# Schematic.net
KiCad netlist of a schematic drawn in EAGLE
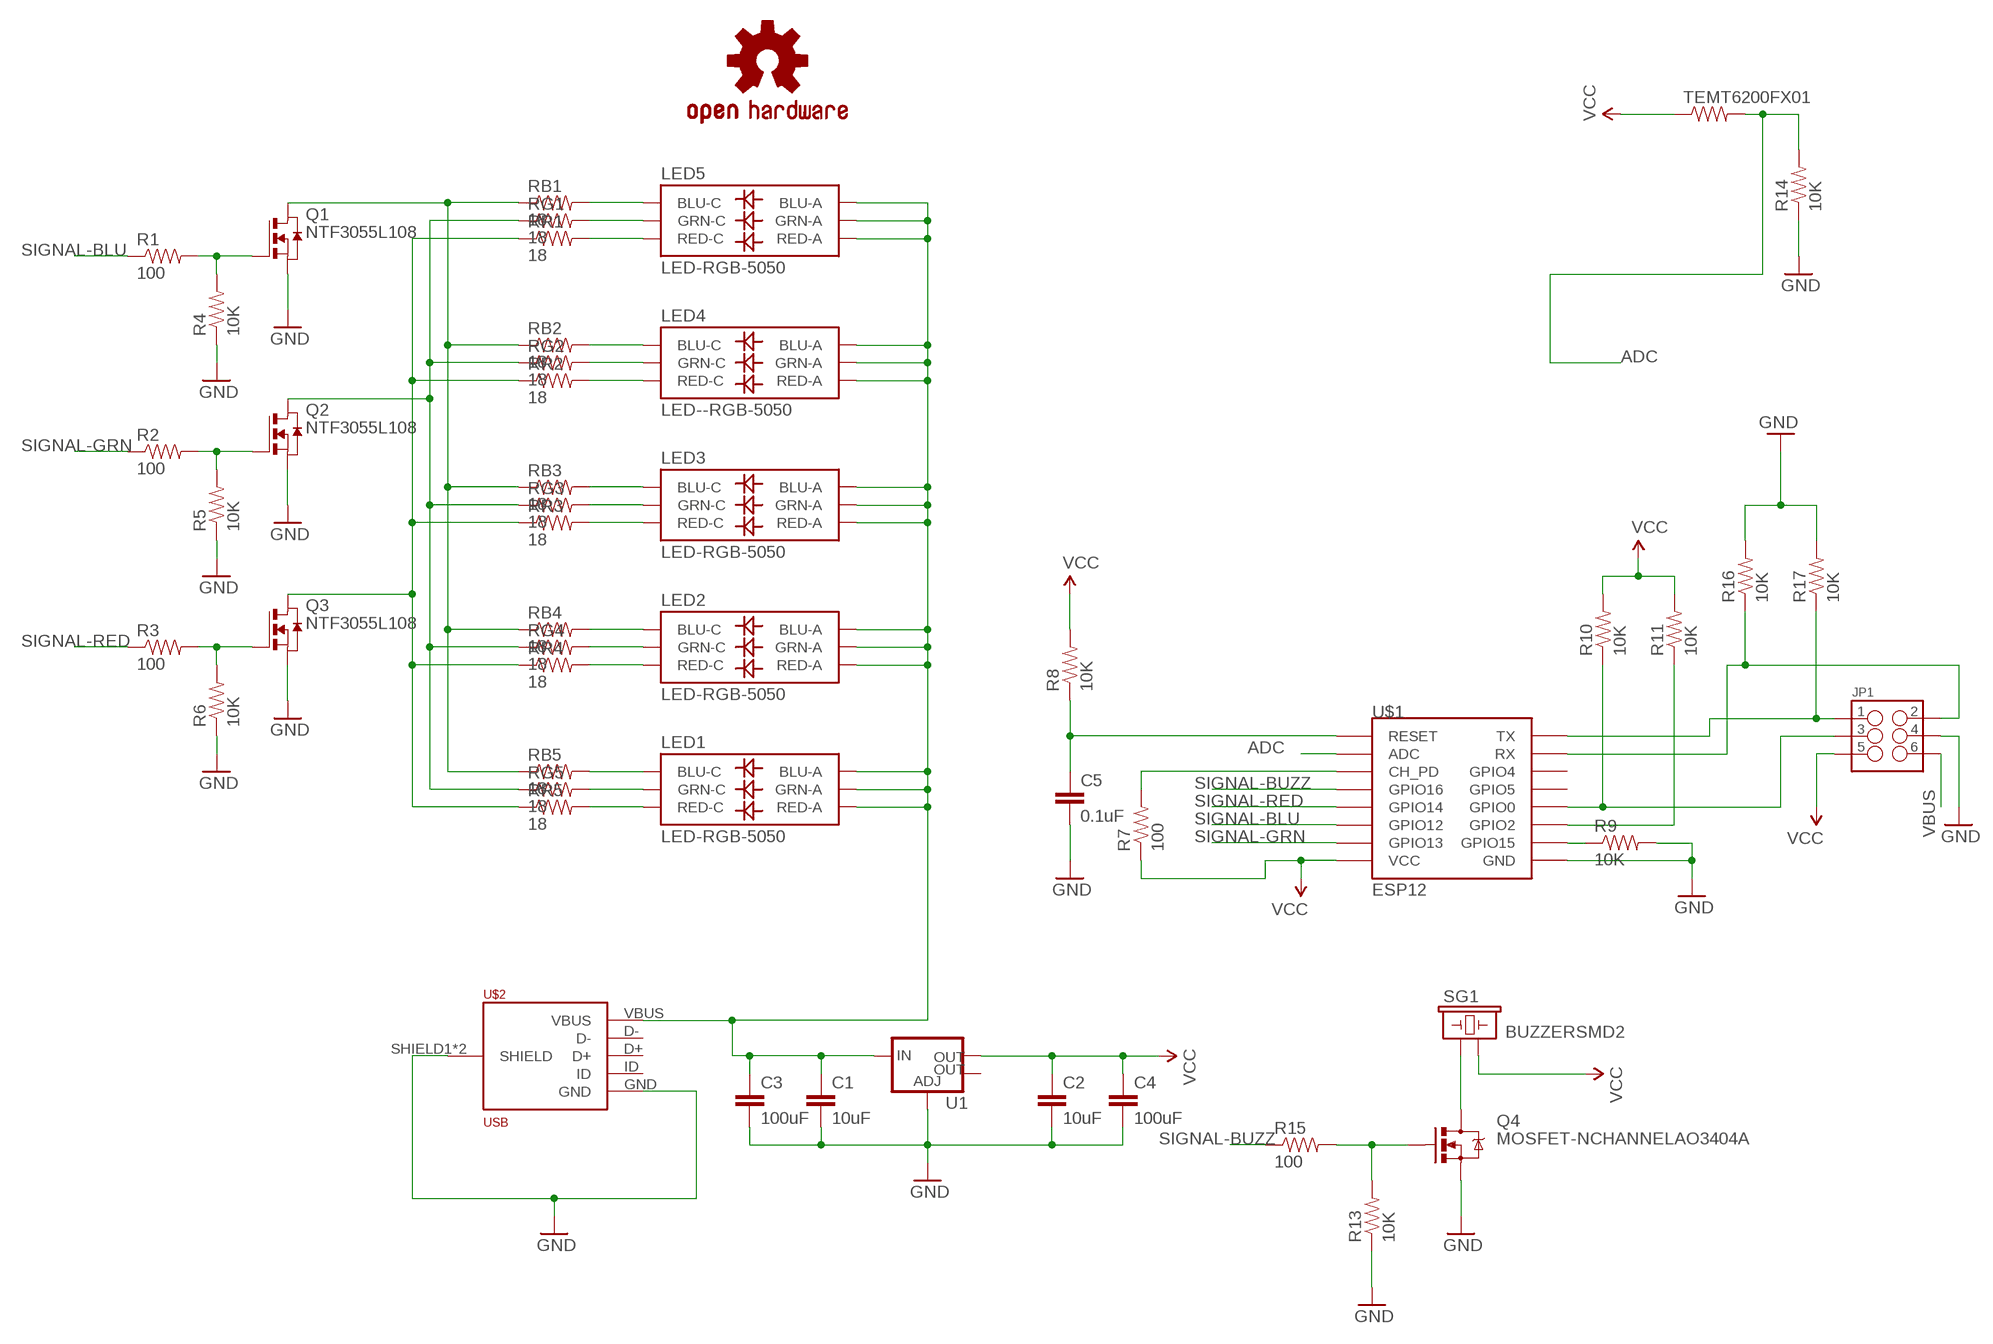
[diagram p0: schematic, sheet 1]

(export (version "E")
  (design (tool "Eeschema 10.0.6"))
  (components
    (comp (ref "C1")
      (value "10uF")
      (footprint "eagle-import:0603-CAP")
      (libsource (lib "eagle-import") (part "CAP0603-CAP"))
    )
    (comp (ref "C2")
      (value "10uF")
      (footprint "eagle-import:0603-CAP")
      (libsource (lib "eagle-import") (part "CAP0603-CAP"))
    )
    (comp (ref "C3")
      (value "100uF")
      (footprint "eagle-import:1206")
      (libsource (lib "eagle-import") (part "CAP1206"))
    )
    (comp (ref "C4")
      (value "100uF")
      (footprint "eagle-import:1206")
      (libsource (lib "eagle-import") (part "CAP1206"))
    )
    (comp (ref "C5")
      (value "0.1uF")
      (footprint "eagle-import:0603-CAP")
      (libsource (lib "eagle-import") (part "CAP0603-CAP"))
    )
    (comp (ref "JP1")
      (value "M03X2POGO_PINS")
      (footprint "eagle-import:2X3_POGO")
      (libsource (lib "eagle-import") (part "M03X2POGO_PINS"))
    )
    (comp (ref "LED1")
      (value "LED-RGB-5050")
      (footprint "eagle-import:LED-TRICOLOR-5050")
      (libsource (lib "eagle-import") (part "LED-TRICOLOR-5050NO_IC"))
    )
    (comp (ref "LED2")
      (value "LED-RGB-5050")
      (footprint "eagle-import:LED-TRICOLOR-5050")
      (libsource (lib "eagle-import") (part "LED-TRICOLOR-5050NO_IC"))
    )
    (comp (ref "LED3")
      (value "LED-RGB-5050")
      (footprint "eagle-import:LED-TRICOLOR-5050")
      (libsource (lib "eagle-import") (part "LED-TRICOLOR-5050NO_IC"))
    )
    (comp (ref "LED4")
      (value "LED--RGB-5050")
      (footprint "eagle-import:LED-TRICOLOR-5050")
      (libsource (lib "eagle-import") (part "LED-TRICOLOR-5050NO_IC"))
    )
    (comp (ref "LED5")
      (value "LED-RGB-5050")
      (footprint "eagle-import:LED-TRICOLOR-5050")
      (libsource (lib "eagle-import") (part "LED-TRICOLOR-5050NO_IC"))
    )
    (comp (ref "LOGO1")
      (value "OSHW-LOGOM-COPPER")
      (footprint "eagle-import:OSHW-LOGO-M_COPPER")
      (libsource (lib "eagle-import") (part "OSHW-LOGOM-COPPER"))
    )
    (comp (ref "Q1")
      (value "NTF3055L108")
      (footprint "eagle-import:SOT223HEAT")
      (libsource (lib "eagle-import") (part "NMOSSOT223'HEATSINK'"))
    )
    (comp (ref "Q2")
      (value "NTF3055L108")
      (footprint "eagle-import:SOT223HEAT")
      (libsource (lib "eagle-import") (part "NMOSSOT223'HEATSINK'"))
    )
    (comp (ref "Q3")
      (value "NTF3055L108")
      (footprint "eagle-import:SOT223HEAT")
      (libsource (lib "eagle-import") (part "NMOSSOT223'HEATSINK'"))
    )
    (comp (ref "Q4")
      (value "MOSFET-NCHANNELAO3404A")
      (footprint "eagle-import:SOT23-3")
      (libsource (lib "eagle-import") (part "MOSFET-NCHANNELAO3404A"))
    )
    (comp (ref "R1")
      (value "100")
      (footprint "eagle-import:0805")
      (libsource (lib "eagle-import") (part "RESISTOR0805-RES"))
    )
    (comp (ref "R2")
      (value "100")
      (footprint "eagle-import:0805")
      (libsource (lib "eagle-import") (part "RESISTOR0805-RES"))
    )
    (comp (ref "R3")
      (value "100")
      (footprint "eagle-import:0805")
      (libsource (lib "eagle-import") (part "RESISTOR0805-RES"))
    )
    (comp (ref "R4")
      (value "10K")
      (footprint "eagle-import:0805")
      (libsource (lib "eagle-import") (part "RESISTOR0805-RES"))
    )
    (comp (ref "R5")
      (value "10K")
      (footprint "eagle-import:0805")
      (libsource (lib "eagle-import") (part "RESISTOR0805-RES"))
    )
    (comp (ref "R6")
      (value "10K")
      (footprint "eagle-import:0805")
      (libsource (lib "eagle-import") (part "RESISTOR0805-RES"))
    )
    (comp (ref "R7")
      (value "100")
      (footprint "eagle-import:0805")
      (libsource (lib "eagle-import") (part "RESISTOR0805-RES"))
    )
    (comp (ref "R8")
      (value "10K")
      (footprint "eagle-import:0805")
      (libsource (lib "eagle-import") (part "RESISTOR0805-RES"))
    )
    (comp (ref "R9")
      (value "10K")
      (footprint "eagle-import:0805")
      (libsource (lib "eagle-import") (part "RESISTOR0805-RES"))
    )
    (comp (ref "R10")
      (value "10K")
      (footprint "eagle-import:0805")
      (libsource (lib "eagle-import") (part "RESISTOR0805-RES"))
    )
    (comp (ref "R11")
      (value "10K")
      (footprint "eagle-import:0805")
      (libsource (lib "eagle-import") (part "RESISTOR0805-RES"))
    )
    (comp (ref "R13")
      (value "10K")
      (footprint "eagle-import:0805")
      (libsource (lib "eagle-import") (part "RESISTOR0805-RES"))
    )
    (comp (ref "R14")
      (value "10K")
      (footprint "eagle-import:0805")
      (libsource (lib "eagle-import") (part "RESISTOR0805-RES"))
    )
    (comp (ref "R15")
      (value "100")
      (footprint "eagle-import:0805")
      (libsource (lib "eagle-import") (part "RESISTOR0805-RES"))
    )
    (comp (ref "R16")
      (value "10K")
      (footprint "eagle-import:0805")
      (libsource (lib "eagle-import") (part "RESISTOR0805-RES"))
    )
    (comp (ref "R17")
      (value "10K")
      (footprint "eagle-import:0805")
      (libsource (lib "eagle-import") (part "RESISTOR0805-RES"))
    )
    (comp (ref "RB1")
      (value "18")
      (footprint "eagle-import:1206")
      (libsource (lib "eagle-import") (part "RESISTOR1206"))
    )
    (comp (ref "RB2")
      (value "18")
      (footprint "eagle-import:1206")
      (libsource (lib "eagle-import") (part "RESISTOR1206"))
    )
    (comp (ref "RB3")
      (value "18")
      (footprint "eagle-import:1206")
      (libsource (lib "eagle-import") (part "RESISTOR1206"))
    )
    (comp (ref "RB4")
      (value "18")
      (footprint "eagle-import:1206")
      (libsource (lib "eagle-import") (part "RESISTOR1206"))
    )
    (comp (ref "RB5")
      (value "18")
      (footprint "eagle-import:1206")
      (libsource (lib "eagle-import") (part "RESISTOR1206"))
    )
    (comp (ref "RG1")
      (value "18")
      (footprint "eagle-import:1206")
      (libsource (lib "eagle-import") (part "RESISTOR1206"))
    )
    (comp (ref "RG2")
      (value "18")
      (footprint "eagle-import:1206")
      (libsource (lib "eagle-import") (part "RESISTOR1206"))
    )
    (comp (ref "RG3")
      (value "18")
      (footprint "eagle-import:1206")
      (libsource (lib "eagle-import") (part "RESISTOR1206"))
    )
    (comp (ref "RG4")
      (value "18")
      (footprint "eagle-import:1206")
      (libsource (lib "eagle-import") (part "RESISTOR1206"))
    )
    (comp (ref "RG5")
      (value "18")
      (footprint "eagle-import:1206")
      (libsource (lib "eagle-import") (part "RESISTOR1206"))
    )
    (comp (ref "RR1")
      (value "18")
      (footprint "eagle-import:1206")
      (libsource (lib "eagle-import") (part "RESISTOR1206"))
    )
    (comp (ref "RR2")
      (value "18")
      (footprint "eagle-import:1206")
      (libsource (lib "eagle-import") (part "RESISTOR1206"))
    )
    (comp (ref "RR3")
      (value "18")
      (footprint "eagle-import:1206")
      (libsource (lib "eagle-import") (part "RESISTOR1206"))
    )
    (comp (ref "RR4")
      (value "18")
      (footprint "eagle-import:1206")
      (libsource (lib "eagle-import") (part "RESISTOR1206"))
    )
    (comp (ref "RR5")
      (value "18")
      (footprint "eagle-import:1206")
      (libsource (lib "eagle-import") (part "RESISTOR1206"))
    )
    (comp (ref "SG1")
      (value "BUZZERSMD2")
      (footprint "eagle-import:BUZZER-CCV")
      (libsource (lib "eagle-import") (part "BUZZERSMD2"))
    )
    (comp (ref "TEMT6200FX01")
      (value "RESISTOR0805-RES")
      (footprint "eagle-import:0805")
      (libsource (lib "eagle-import") (part "RESISTOR0805-RES"))
    )
    (comp (ref "U$1")
      (value "ESP12")
      (footprint "eagle-import:ESP12")
      (libsource (lib "eagle-import") (part "ESP12"))
    )
    (comp (ref "U$2")
      (value "USB")
      (footprint "eagle-import:MICRO-USB3065-30-00-A")
      (libsource (lib "eagle-import") (part "USB"))
    )
    (comp (ref "U1")
      (value "V_REG_LM1117SOT223")
      (footprint "eagle-import:SOT223")
      (libsource (lib "eagle-import") (part "V_REG_LM1117SOT223"))
    )
  )
  (nets
    (net (code "1") (name "/ADC") (class "Default")
      (node (ref "R14") (pin "2") (pinfunction "2_2") (pintype "passive"))
      (node (ref "TEMT6200FX01") (pin "2") (pinfunction "2_2") (pintype "passive"))
      (node (ref "U$1") (pin "ADC") (pinfunction "ADC_ADC") (pintype "bidirectional"))
    )
    (net (code "2") (name "/SIGNAL-BLU") (class "Default")
      (node (ref "R1") (pin "1") (pinfunction "1_1") (pintype "passive"))
      (node (ref "U$1") (pin "GPIO12") (pinfunction "GPIO12_GPIO12") (pintype "bidirectional"))
    )
    (net (code "3") (name "/SIGNAL-BUZZ") (class "Default")
      (node (ref "R15") (pin "1") (pinfunction "1_1") (pintype "passive"))
      (node (ref "U$1") (pin "GPIO16") (pinfunction "GPIO16_GPIO16") (pintype "bidirectional"))
    )
    (net (code "4") (name "/SIGNAL-GRN") (class "Default")
      (node (ref "R2") (pin "1") (pinfunction "1_1") (pintype "passive"))
      (node (ref "U$1") (pin "GPIO13") (pinfunction "GPIO13_GPIO13") (pintype "bidirectional"))
    )
    (net (code "5") (name "/SIGNAL-RED") (class "Default")
      (node (ref "R3") (pin "1") (pinfunction "1_1") (pintype "passive"))
      (node (ref "U$1") (pin "GPIO14") (pinfunction "GPIO14_GPIO14") (pintype "bidirectional"))
    )
    (net (code "6") (name "/VBUS") (class "Default")
      (node (ref "C1") (pin "1") (pinfunction "1_1") (pintype "passive"))
      (node (ref "C3") (pin "1") (pinfunction "1_1") (pintype "passive"))
      (node (ref "JP1") (pin "P$6") (pinfunction "6_P$6") (pintype "bidirectional"))
      (node (ref "LED1") (pin "1") (pinfunction "GRN-A_1") (pintype "bidirectional"))
      (node (ref "LED1") (pin "2") (pinfunction "RED-A_2") (pintype "bidirectional"))
      (node (ref "LED1") (pin "3") (pinfunction "BLU-A_3") (pintype "bidirectional"))
      (node (ref "LED2") (pin "1") (pinfunction "GRN-A_1") (pintype "bidirectional"))
      (node (ref "LED2") (pin "2") (pinfunction "RED-A_2") (pintype "bidirectional"))
      (node (ref "LED2") (pin "3") (pinfunction "BLU-A_3") (pintype "bidirectional"))
      (node (ref "LED3") (pin "1") (pinfunction "GRN-A_1") (pintype "bidirectional"))
      (node (ref "LED3") (pin "2") (pinfunction "RED-A_2") (pintype "bidirectional"))
      (node (ref "LED3") (pin "3") (pinfunction "BLU-A_3") (pintype "bidirectional"))
      (node (ref "LED4") (pin "1") (pinfunction "GRN-A_1") (pintype "bidirectional"))
      (node (ref "LED4") (pin "2") (pinfunction "RED-A_2") (pintype "bidirectional"))
      (node (ref "LED4") (pin "3") (pinfunction "BLU-A_3") (pintype "bidirectional"))
      (node (ref "LED5") (pin "1") (pinfunction "GRN-A_1") (pintype "bidirectional"))
      (node (ref "LED5") (pin "2") (pinfunction "RED-A_2") (pintype "bidirectional"))
      (node (ref "LED5") (pin "3") (pinfunction "BLU-A_3") (pintype "bidirectional"))
      (node (ref "U$2") (pin "VBUS") (pinfunction "VBUS_VBUS") (pintype "bidirectional"))
      (node (ref "U1") (pin "3") (pinfunction "IN_3") (pintype "input"))
    )
    (net (code "7") (name "GND") (class "Default")
      (node (ref "C1") (pin "2") (pinfunction "2_2") (pintype "passive"))
      (node (ref "C2") (pin "2") (pinfunction "2_2") (pintype "passive"))
      (node (ref "C3") (pin "2") (pinfunction "2_2") (pintype "passive"))
      (node (ref "C4") (pin "2") (pinfunction "2_2") (pintype "passive"))
      (node (ref "C5") (pin "2") (pinfunction "2_2") (pintype "passive"))
      (node (ref "JP1") (pin "P$4") (pinfunction "4_P$4") (pintype "bidirectional"))
      (node (ref "Q1") (pin "3") (pinfunction "S_3") (pintype "passive"))
      (node (ref "Q2") (pin "3") (pinfunction "S_3") (pintype "passive"))
      (node (ref "Q3") (pin "3") (pinfunction "S_3") (pintype "passive"))
      (node (ref "Q4") (pin "2") (pinfunction "S_2") (pintype "passive"))
      (node (ref "R13") (pin "1") (pinfunction "1_1") (pintype "passive"))
      (node (ref "R14") (pin "1") (pinfunction "1_1") (pintype "passive"))
      (node (ref "R16") (pin "2") (pinfunction "2_2") (pintype "passive"))
      (node (ref "R17") (pin "2") (pinfunction "2_2") (pintype "passive"))
      (node (ref "R4") (pin "1") (pinfunction "1_1") (pintype "passive"))
      (node (ref "R5") (pin "1") (pinfunction "1_1") (pintype "passive"))
      (node (ref "R6") (pin "1") (pinfunction "1_1") (pintype "passive"))
      (node (ref "R9") (pin "2") (pinfunction "2_2") (pintype "passive"))
      (node (ref "U$1") (pin "GND") (pinfunction "GND_GND") (pintype "bidirectional"))
      (node (ref "U$2") (pin "GND") (pinfunction "GND_GND") (pintype "bidirectional"))
      (node (ref "U$2") (pin "SHIELD1") (pinfunction "SHIELD_SHIELD1") (pintype "bidirectional"))
      (node (ref "U$2") (pin "SHIELD2") (pinfunction "SHIELD_SHIELD2") (pintype "bidirectional"))
      (node (ref "U1") (pin "1") (pinfunction "ADJ_1") (pintype "input"))
    )
    (net (code "8") (name "Net-(C5-Pad1)") (class "Default")
      (node (ref "C5") (pin "1") (pinfunction "1_1") (pintype "passive"))
      (node (ref "R8") (pin "1") (pinfunction "1_1") (pintype "passive"))
      (node (ref "U$1") (pin "RESET") (pinfunction "RESET_RESET") (pintype "bidirectional"))
    )
    (net (code "9") (name "Net-(JP1-1)") (class "Default")
      (node (ref "JP1") (pin "P$1") (pinfunction "1_P$1") (pintype "bidirectional"))
      (node (ref "R17") (pin "1") (pinfunction "1_1") (pintype "passive"))
      (node (ref "U$1") (pin "TX") (pinfunction "TX_TX") (pintype "bidirectional"))
    )
    (net (code "10") (name "Net-(JP1-2)") (class "Default")
      (node (ref "JP1") (pin "P$2") (pinfunction "2_P$2") (pintype "bidirectional"))
      (node (ref "R16") (pin "1") (pinfunction "1_1") (pintype "passive"))
      (node (ref "U$1") (pin "RX") (pinfunction "RX_RX") (pintype "bidirectional"))
    )
    (net (code "11") (name "Net-(JP1-3)") (class "Default")
      (node (ref "JP1") (pin "P$3") (pinfunction "3_P$3") (pintype "bidirectional"))
      (node (ref "R10") (pin "1") (pinfunction "1_1") (pintype "passive"))
      (node (ref "U$1") (pin "GPIO0") (pinfunction "GPIO0_GPIO0") (pintype "bidirectional"))
    )
    (net (code "12") (name "Net-(LED1-BLU-C)") (class "Default")
      (node (ref "LED1") (pin "4") (pinfunction "BLU-C_4") (pintype "bidirectional"))
      (node (ref "RB5") (pin "2") (pinfunction "2_2") (pintype "passive"))
    )
    (net (code "13") (name "Net-(LED1-GRN-C)") (class "Default")
      (node (ref "LED1") (pin "6") (pinfunction "GRN-C_6") (pintype "bidirectional"))
      (node (ref "RG5") (pin "2") (pinfunction "2_2") (pintype "passive"))
    )
    (net (code "14") (name "Net-(LED1-RED-C)") (class "Default")
      (node (ref "LED1") (pin "5") (pinfunction "RED-C_5") (pintype "bidirectional"))
      (node (ref "RR5") (pin "2") (pinfunction "2_2") (pintype "passive"))
    )
    (net (code "15") (name "Net-(LED2-BLU-C)") (class "Default")
      (node (ref "LED2") (pin "4") (pinfunction "BLU-C_4") (pintype "bidirectional"))
      (node (ref "RB4") (pin "2") (pinfunction "2_2") (pintype "passive"))
    )
    (net (code "16") (name "Net-(LED2-GRN-C)") (class "Default")
      (node (ref "LED2") (pin "6") (pinfunction "GRN-C_6") (pintype "bidirectional"))
      (node (ref "RG4") (pin "2") (pinfunction "2_2") (pintype "passive"))
    )
    (net (code "17") (name "Net-(LED2-RED-C)") (class "Default")
      (node (ref "LED2") (pin "5") (pinfunction "RED-C_5") (pintype "bidirectional"))
      (node (ref "RR4") (pin "2") (pinfunction "2_2") (pintype "passive"))
    )
    (net (code "18") (name "Net-(LED3-BLU-C)") (class "Default")
      (node (ref "LED3") (pin "4") (pinfunction "BLU-C_4") (pintype "bidirectional"))
      (node (ref "RB3") (pin "2") (pinfunction "2_2") (pintype "passive"))
    )
    (net (code "19") (name "Net-(LED3-GRN-C)") (class "Default")
      (node (ref "LED3") (pin "6") (pinfunction "GRN-C_6") (pintype "bidirectional"))
      (node (ref "RG3") (pin "2") (pinfunction "2_2") (pintype "passive"))
    )
    (net (code "20") (name "Net-(LED3-RED-C)") (class "Default")
      (node (ref "LED3") (pin "5") (pinfunction "RED-C_5") (pintype "bidirectional"))
      (node (ref "RR3") (pin "2") (pinfunction "2_2") (pintype "passive"))
    )
    (net (code "21") (name "Net-(LED4-BLU-C)") (class "Default")
      (node (ref "LED4") (pin "4") (pinfunction "BLU-C_4") (pintype "bidirectional"))
      (node (ref "RB2") (pin "2") (pinfunction "2_2") (pintype "passive"))
    )
    (net (code "22") (name "Net-(LED4-GRN-C)") (class "Default")
      (node (ref "LED4") (pin "6") (pinfunction "GRN-C_6") (pintype "bidirectional"))
      (node (ref "RG2") (pin "2") (pinfunction "2_2") (pintype "passive"))
    )
    (net (code "23") (name "Net-(LED4-RED-C)") (class "Default")
      (node (ref "LED4") (pin "5") (pinfunction "RED-C_5") (pintype "bidirectional"))
      (node (ref "RR2") (pin "2") (pinfunction "2_2") (pintype "passive"))
    )
    (net (code "24") (name "Net-(LED5-BLU-C)") (class "Default")
      (node (ref "LED5") (pin "4") (pinfunction "BLU-C_4") (pintype "bidirectional"))
      (node (ref "RB1") (pin "2") (pinfunction "2_2") (pintype "passive"))
    )
    (net (code "25") (name "Net-(LED5-GRN-C)") (class "Default")
      (node (ref "LED5") (pin "6") (pinfunction "GRN-C_6") (pintype "bidirectional"))
      (node (ref "RG1") (pin "2") (pinfunction "2_2") (pintype "passive"))
    )
    (net (code "26") (name "Net-(LED5-RED-C)") (class "Default")
      (node (ref "LED5") (pin "5") (pinfunction "RED-C_5") (pintype "bidirectional"))
      (node (ref "RR1") (pin "2") (pinfunction "2_2") (pintype "passive"))
    )
    (net (code "27") (name "Net-(Q1-D-Pad2)") (class "Default")
      (node (ref "Q1") (pin "2") (pinfunction "D_2") (pintype "passive"))
      (node (ref "Q1") (pin "4") (pinfunction "D_4") (pintype "passive"))
      (node (ref "Q1") (pin "P$1") (pinfunction "D_P$1") (pintype "passive"))
      (node (ref "Q1") (pin "P$10") (pinfunction "D_P$10") (pintype "passive"))
      (node (ref "Q1") (pin "P$11") (pinfunction "D_P$11") (pintype "passive"))
      (node (ref "Q1") (pin "P$12") (pinfunction "D_P$12") (pintype "passive"))
      (node (ref "Q1") (pin "P$13") (pinfunction "D_P$13") (pintype "passive"))
      (node (ref "Q1") (pin "P$14") (pinfunction "D_P$14") (pintype "passive"))
      (node (ref "Q1") (pin "P$15") (pinfunction "D_P$15") (pintype "passive"))
      (node (ref "Q1") (pin "P$16") (pinfunction "D_P$16") (pintype "passive"))
      (node (ref "Q1") (pin "P$17") (pinfunction "D_P$17") (pintype "passive"))
      (node (ref "Q1") (pin "P$18") (pinfunction "D_P$18") (pintype "passive"))
      (node (ref "Q1") (pin "P$19") (pinfunction "D_P$19") (pintype "passive"))
      (node (ref "Q1") (pin "P$2") (pinfunction "D_P$2") (pintype "passive"))
      (node (ref "Q1") (pin "P$3") (pinfunction "D_P$3") (pintype "passive"))
      (node (ref "Q1") (pin "P$4") (pinfunction "D_P$4") (pintype "passive"))
      (node (ref "Q1") (pin "P$5") (pinfunction "D_P$5") (pintype "passive"))
      (node (ref "Q1") (pin "P$6") (pinfunction "D_P$6") (pintype "passive"))
      (node (ref "Q1") (pin "P$7") (pinfunction "D_P$7") (pintype "passive"))
      (node (ref "Q1") (pin "P$8") (pinfunction "D_P$8") (pintype "passive"))
      (node (ref "Q1") (pin "P$9") (pinfunction "D_P$9") (pintype "passive"))
      (node (ref "RB1") (pin "1") (pinfunction "1_1") (pintype "passive"))
      (node (ref "RB2") (pin "1") (pinfunction "1_1") (pintype "passive"))
      (node (ref "RB3") (pin "1") (pinfunction "1_1") (pintype "passive"))
      (node (ref "RB4") (pin "1") (pinfunction "1_1") (pintype "passive"))
      (node (ref "RB5") (pin "1") (pinfunction "1_1") (pintype "passive"))
    )
    (net (code "28") (name "Net-(Q1-G)") (class "Default")
      (node (ref "Q1") (pin "1") (pinfunction "G_1") (pintype "passive"))
      (node (ref "R1") (pin "2") (pinfunction "2_2") (pintype "passive"))
      (node (ref "R4") (pin "2") (pinfunction "2_2") (pintype "passive"))
    )
    (net (code "29") (name "Net-(Q2-D-Pad2)") (class "Default")
      (node (ref "Q2") (pin "2") (pinfunction "D_2") (pintype "passive"))
      (node (ref "Q2") (pin "4") (pinfunction "D_4") (pintype "passive"))
      (node (ref "Q2") (pin "P$1") (pinfunction "D_P$1") (pintype "passive"))
      (node (ref "Q2") (pin "P$10") (pinfunction "D_P$10") (pintype "passive"))
      (node (ref "Q2") (pin "P$11") (pinfunction "D_P$11") (pintype "passive"))
      (node (ref "Q2") (pin "P$12") (pinfunction "D_P$12") (pintype "passive"))
      (node (ref "Q2") (pin "P$13") (pinfunction "D_P$13") (pintype "passive"))
      (node (ref "Q2") (pin "P$14") (pinfunction "D_P$14") (pintype "passive"))
      (node (ref "Q2") (pin "P$15") (pinfunction "D_P$15") (pintype "passive"))
      (node (ref "Q2") (pin "P$16") (pinfunction "D_P$16") (pintype "passive"))
      (node (ref "Q2") (pin "P$17") (pinfunction "D_P$17") (pintype "passive"))
      (node (ref "Q2") (pin "P$18") (pinfunction "D_P$18") (pintype "passive"))
      (node (ref "Q2") (pin "P$19") (pinfunction "D_P$19") (pintype "passive"))
      (node (ref "Q2") (pin "P$2") (pinfunction "D_P$2") (pintype "passive"))
      (node (ref "Q2") (pin "P$3") (pinfunction "D_P$3") (pintype "passive"))
      (node (ref "Q2") (pin "P$4") (pinfunction "D_P$4") (pintype "passive"))
      (node (ref "Q2") (pin "P$5") (pinfunction "D_P$5") (pintype "passive"))
      (node (ref "Q2") (pin "P$6") (pinfunction "D_P$6") (pintype "passive"))
      (node (ref "Q2") (pin "P$7") (pinfunction "D_P$7") (pintype "passive"))
      (node (ref "Q2") (pin "P$8") (pinfunction "D_P$8") (pintype "passive"))
      (node (ref "Q2") (pin "P$9") (pinfunction "D_P$9") (pintype "passive"))
      (node (ref "RG1") (pin "1") (pinfunction "1_1") (pintype "passive"))
      (node (ref "RG2") (pin "1") (pinfunction "1_1") (pintype "passive"))
      (node (ref "RG3") (pin "1") (pinfunction "1_1") (pintype "passive"))
      (node (ref "RG4") (pin "1") (pinfunction "1_1") (pintype "passive"))
      (node (ref "RG5") (pin "1") (pinfunction "1_1") (pintype "passive"))
    )
    (net (code "30") (name "Net-(Q2-G)") (class "Default")
      (node (ref "Q2") (pin "1") (pinfunction "G_1") (pintype "passive"))
      (node (ref "R2") (pin "2") (pinfunction "2_2") (pintype "passive"))
      (node (ref "R5") (pin "2") (pinfunction "2_2") (pintype "passive"))
    )
    (net (code "31") (name "Net-(Q3-D-Pad2)") (class "Default")
      (node (ref "Q3") (pin "2") (pinfunction "D_2") (pintype "passive"))
      (node (ref "Q3") (pin "4") (pinfunction "D_4") (pintype "passive"))
      (node (ref "Q3") (pin "P$1") (pinfunction "D_P$1") (pintype "passive"))
      (node (ref "Q3") (pin "P$10") (pinfunction "D_P$10") (pintype "passive"))
      (node (ref "Q3") (pin "P$11") (pinfunction "D_P$11") (pintype "passive"))
      (node (ref "Q3") (pin "P$12") (pinfunction "D_P$12") (pintype "passive"))
      (node (ref "Q3") (pin "P$13") (pinfunction "D_P$13") (pintype "passive"))
      (node (ref "Q3") (pin "P$14") (pinfunction "D_P$14") (pintype "passive"))
      (node (ref "Q3") (pin "P$15") (pinfunction "D_P$15") (pintype "passive"))
      (node (ref "Q3") (pin "P$16") (pinfunction "D_P$16") (pintype "passive"))
      (node (ref "Q3") (pin "P$17") (pinfunction "D_P$17") (pintype "passive"))
      (node (ref "Q3") (pin "P$18") (pinfunction "D_P$18") (pintype "passive"))
      (node (ref "Q3") (pin "P$19") (pinfunction "D_P$19") (pintype "passive"))
      (node (ref "Q3") (pin "P$2") (pinfunction "D_P$2") (pintype "passive"))
      (node (ref "Q3") (pin "P$3") (pinfunction "D_P$3") (pintype "passive"))
      (node (ref "Q3") (pin "P$4") (pinfunction "D_P$4") (pintype "passive"))
      (node (ref "Q3") (pin "P$5") (pinfunction "D_P$5") (pintype "passive"))
      (node (ref "Q3") (pin "P$6") (pinfunction "D_P$6") (pintype "passive"))
      (node (ref "Q3") (pin "P$7") (pinfunction "D_P$7") (pintype "passive"))
      (node (ref "Q3") (pin "P$8") (pinfunction "D_P$8") (pintype "passive"))
      (node (ref "Q3") (pin "P$9") (pinfunction "D_P$9") (pintype "passive"))
      (node (ref "RR1") (pin "1") (pinfunction "1_1") (pintype "passive"))
      (node (ref "RR2") (pin "1") (pinfunction "1_1") (pintype "passive"))
      (node (ref "RR3") (pin "1") (pinfunction "1_1") (pintype "passive"))
      (node (ref "RR4") (pin "1") (pinfunction "1_1") (pintype "passive"))
      (node (ref "RR5") (pin "1") (pinfunction "1_1") (pintype "passive"))
    )
    (net (code "32") (name "Net-(Q3-G)") (class "Default")
      (node (ref "Q3") (pin "1") (pinfunction "G_1") (pintype "passive"))
      (node (ref "R3") (pin "2") (pinfunction "2_2") (pintype "passive"))
      (node (ref "R6") (pin "2") (pinfunction "2_2") (pintype "passive"))
    )
    (net (code "33") (name "Net-(Q4-D)") (class "Default")
      (node (ref "Q4") (pin "3") (pinfunction "D_3") (pintype "passive"))
      (node (ref "SG1") (pin "+") (pinfunction "1_+") (pintype "passive"))
    )
    (net (code "34") (name "Net-(Q4-G)") (class "Default")
      (node (ref "Q4") (pin "1") (pinfunction "G_1") (pintype "passive"))
      (node (ref "R13") (pin "2") (pinfunction "2_2") (pintype "passive"))
      (node (ref "R15") (pin "2") (pinfunction "2_2") (pintype "passive"))
    )
    (net (code "35") (name "Net-(R7-Pad2)") (class "Default")
      (node (ref "R7") (pin "2") (pinfunction "2_2") (pintype "passive"))
      (node (ref "U$1") (pin "CH_PD") (pinfunction "CH_PD_CH_PD") (pintype "bidirectional"))
    )
    (net (code "36") (name "Net-(R9-Pad1)") (class "Default")
      (node (ref "R9") (pin "1") (pinfunction "1_1") (pintype "passive"))
      (node (ref "U$1") (pin "GPIO15") (pinfunction "GPIO15_GPIO15") (pintype "bidirectional"))
    )
    (net (code "37") (name "Net-(R11-Pad1)") (class "Default")
      (node (ref "R11") (pin "1") (pinfunction "1_1") (pintype "passive"))
      (node (ref "U$1") (pin "GPIO2") (pinfunction "GPIO2_GPIO2") (pintype "bidirectional"))
    )
    (net (code "38") (name "VCC") (class "Default")
      (node (ref "C2") (pin "1") (pinfunction "1_1") (pintype "passive"))
      (node (ref "C4") (pin "1") (pinfunction "1_1") (pintype "passive"))
      (node (ref "JP1") (pin "P$5") (pinfunction "5_P$5") (pintype "bidirectional"))
      (node (ref "R10") (pin "2") (pinfunction "2_2") (pintype "passive"))
      (node (ref "R11") (pin "2") (pinfunction "2_2") (pintype "passive"))
      (node (ref "R7") (pin "1") (pinfunction "1_1") (pintype "passive"))
      (node (ref "R8") (pin "2") (pinfunction "2_2") (pintype "passive"))
      (node (ref "SG1") (pin "-") (pinfunction "2_-") (pintype "passive"))
      (node (ref "TEMT6200FX01") (pin "1") (pinfunction "1_1") (pintype "passive"))
      (node (ref "U$1") (pin "VCC") (pinfunction "VCC_VCC") (pintype "bidirectional"))
      (node (ref "U1") (pin "2") (pinfunction "OUT_2") (pintype "power_in"))
    )
    (net (code "39") (name "unconnected-(U$1-PadGPIO4)") (class "Default")
      (node (ref "U$1") (pin "GPIO4") (pinfunction "GPIO4_GPIO4") (pintype "bidirectional"))
    )
    (net (code "40") (name "unconnected-(U$1-PadGPIO5)") (class "Default")
      (node (ref "U$1") (pin "GPIO5") (pinfunction "GPIO5_GPIO5") (pintype "bidirectional"))
    )
    (net (code "41") (name "unconnected-(U$2-PadD+)") (class "Default")
      (node (ref "U$2") (pin "D+") (pinfunction "D+_D+") (pintype "bidirectional"))
    )
    (net (code "42") (name "unconnected-(U$2-PadD-)") (class "Default")
      (node (ref "U$2") (pin "D-") (pinfunction "D-_D-") (pintype "bidirectional"))
    )
    (net (code "43") (name "unconnected-(U$2-PadID)") (class "Default")
      (node (ref "U$2") (pin "ID") (pinfunction "ID_ID") (pintype "bidirectional"))
    )
    (net (code "44") (name "unconnected-(U1-OUT-Pad4)") (class "Default")
      (node (ref "U1") (pin "4") (pinfunction "OUT_4") (pintype "output"))
    )
  )
)
